# dsPIC.net
KiCad netlist of a schematic drawn in EAGLE
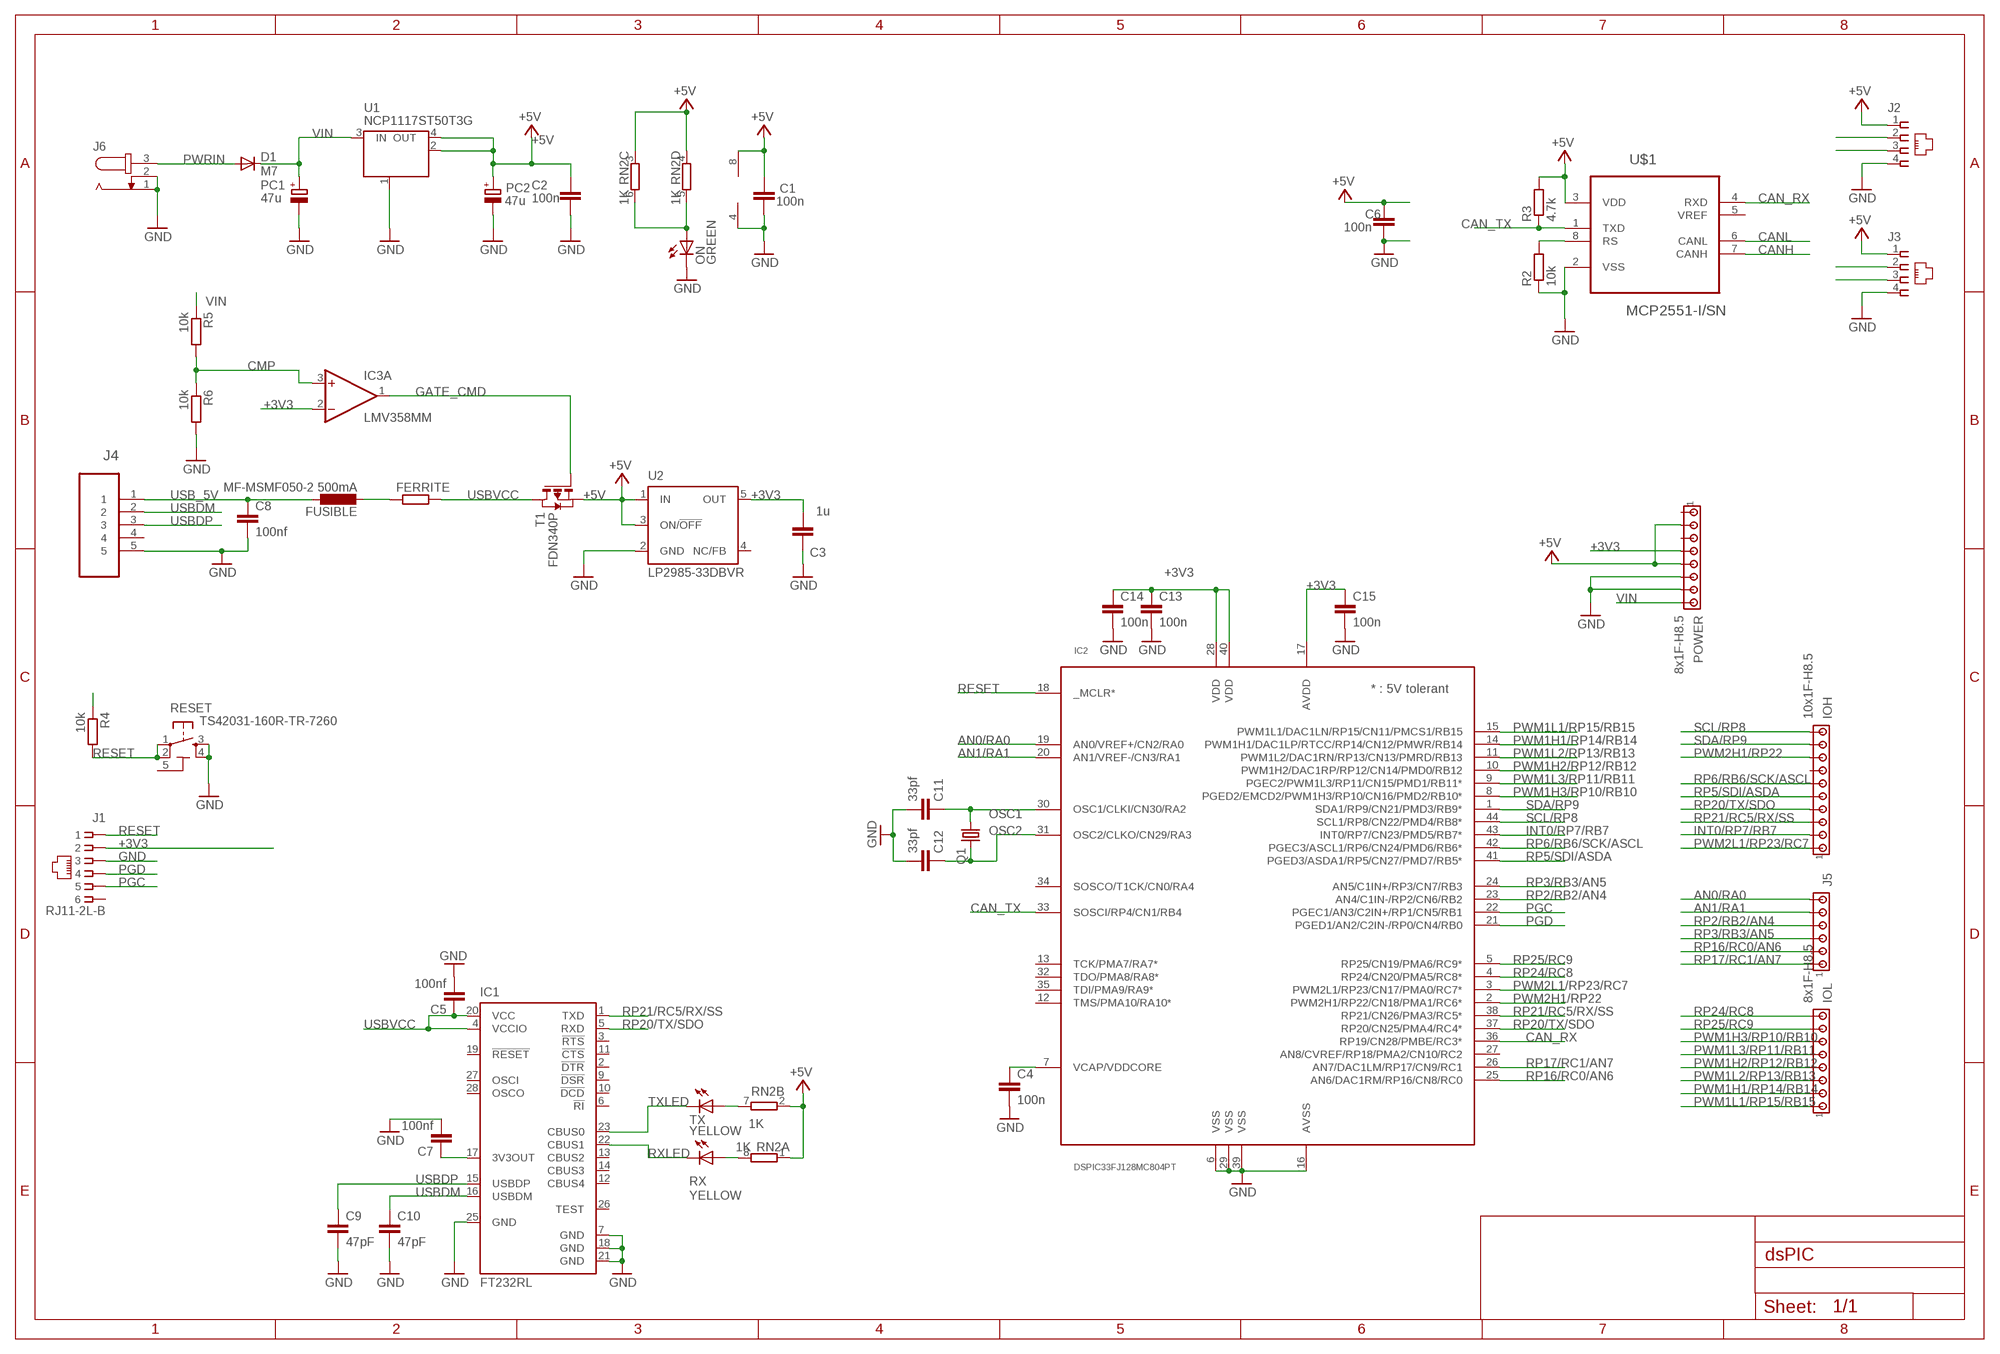
[diagram p0: schematic, sheet 1]

(export (version "E")
  (design (tool "Eeschema 10.0.6"))
  (components
    (comp (ref "C1")
      (value "100n")
      (footprint "eagle-import:C0603-ROUND")
      (libsource (lib "eagle-import") (part "C-EU0603-RND"))
    )
    (comp (ref "C2")
      (value "100n")
      (footprint "eagle-import:C0603-ROUND")
      (libsource (lib "eagle-import") (part "C-EU0603-RND"))
    )
    (comp (ref "C3")
      (value "1u")
      (footprint "eagle-import:C0603-ROUND")
      (libsource (lib "eagle-import") (part "C-EU0603-RND"))
    )
    (comp (ref "C4")
      (value "100n")
      (footprint "eagle-import:C0603K")
      (libsource (lib "eagle-import") (part "SmartPrj_C-EUC0603K"))
    )
    (comp (ref "C5")
      (value "100nf")
      (footprint "eagle-import:C0603")
      (libsource (lib "eagle-import") (part "C-EUC0603"))
    )
    (comp (ref "C6")
      (value "100n")
      (footprint "eagle-import:C0603K")
      (libsource (lib "eagle-import") (part "SmartPrj_C-EUC0603K"))
    )
    (comp (ref "C7")
      (value "100nf")
      (footprint "eagle-import:C0603")
      (libsource (lib "eagle-import") (part "C-EUC0603"))
    )
    (comp (ref "C8")
      (value "100nf")
      (footprint "eagle-import:C0603")
      (libsource (lib "eagle-import") (part "C-EUC0603"))
    )
    (comp (ref "C9")
      (value "47pF")
      (footprint "eagle-import:C0603")
      (libsource (lib "eagle-import") (part "C-EUC0603"))
    )
    (comp (ref "C10")
      (value "47pF")
      (footprint "eagle-import:C0603")
      (libsource (lib "eagle-import") (part "C-EUC0603"))
    )
    (comp (ref "C11")
      (value "33pf")
      (footprint "eagle-import:C0603")
      (libsource (lib "eagle-import") (part "C-EUC0603"))
    )
    (comp (ref "C12")
      (value "33pf")
      (footprint "eagle-import:C0603")
      (libsource (lib "eagle-import") (part "C-EUC0603"))
    )
    (comp (ref "C13")
      (value "100n")
      (footprint "eagle-import:C0603")
      (libsource (lib "eagle-import") (part "C-EUC0603"))
    )
    (comp (ref "C14")
      (value "100n")
      (footprint "eagle-import:C0603")
      (libsource (lib "eagle-import") (part "C-EUC0603"))
    )
    (comp (ref "C15")
      (value "100n")
      (footprint "eagle-import:C0603")
      (libsource (lib "eagle-import") (part "C-EUC0603"))
    )
    (comp (ref "D1")
      (value "M7")
      (footprint "eagle-import:SMB")
      (libsource (lib "eagle-import") (part "DIODE-SMB"))
    )
    (comp (ref "FERRITE")
      (value "R-EU_M0805")
      (footprint "eagle-import:M0805")
      (libsource (lib "eagle-import") (part "R-EU_M0805"))
    )
    (comp (ref "FUSIBLE")
      (value "MF-MSMF050-2 500mA")
      (footprint "eagle-import:L1812")
      (libsource (lib "eagle-import") (part "L-EUL1812"))
    )
    (comp (ref "IC1")
      (value "FT232RL")
      (footprint "eagle-import:SSOP28")
      (libsource (lib "eagle-import") (part "FT232RL"))
    )
    (comp (ref "IC2")
      (value "DSPIC33FJ128MC804PT")
      (footprint "eagle-import:TQFP44")
      (libsource (lib "eagle-import") (part "DSPIC33F04PTJ128MC8"))
    )
    (comp (ref "IC3")
      (value "LMV358MM")
      (footprint "eagle-import:MSOP08")
      (libsource (lib "eagle-import") (part "LMV358?MM"))
    )
    (comp (ref "IOH")
      (value "10x1F-H8.5")
      (footprint "eagle-import:10X10MTA")
      (libsource (lib "eagle-import") (part "MTA10-100"))
    )
    (comp (ref "IOL")
      (value "8x1F-H8.5")
      (footprint "eagle-import:10X08MTA")
      (libsource (lib "eagle-import") (part "MTA08-100"))
    )
    (comp (ref "J1")
      (value "RJ11-2L-B")
      (footprint "eagle-import:RJ11-NO_SHIELD")
      (fields (field (name "MF") "TYCO ELECTRONICS") (field (name "OC_FARNELL") "1393306"))
      (libsource (lib "eagle-import") (part "RJ11-2L-B"))
    )
    (comp (ref "J2")
      (value "520249-2")
      (footprint "eagle-import:520249-2")
      (libsource (lib "eagle-import") (part "520249-2"))
    )
    (comp (ref "J3")
      (value "520249-2")
      (footprint "eagle-import:520249-2")
      (libsource (lib "eagle-import") (part "520249-2"))
    )
    (comp (ref "J4")
      (value "47346-0001")
      (footprint "eagle-import:MOLEX_47346-0001")
      (libsource (lib "eagle-import") (part "47346-0001"))
    )
    (comp (ref "J5")
      (value "MTA06-100")
      (footprint "eagle-import:10X06MTA")
      (libsource (lib "eagle-import") (part "MTA06-100"))
    )
    (comp (ref "J6")
      (value "JACK-PLUG0")
      (footprint "eagle-import:SPC4077")
      (fields (field (name "OC_FARNELL") "1737246"))
      (libsource (lib "eagle-import") (part "JACK-PLUG0"))
    )
    (comp (ref "ON")
      (value "GREEN")
      (footprint "eagle-import:CHIP-LED0805")
      (libsource (lib "eagle-import") (part "LEDCHIP-LED0805"))
    )
    (comp (ref "PC1")
      (value "47u")
      (footprint "eagle-import:PANASONIC_D")
      (libsource (lib "eagle-import") (part "CPOL-EUD"))
    )
    (comp (ref "PC2")
      (value "47u")
      (footprint "eagle-import:PANASONIC_D")
      (libsource (lib "eagle-import") (part "CPOL-EUD"))
    )
    (comp (ref "POWER")
      (value "8x1F-H8.5")
      (footprint "eagle-import:10X08MTA")
      (libsource (lib "eagle-import") (part "MTA08-100"))
    )
    (comp (ref "Q1")
      (value "CRYSTALSM49")
      (footprint "eagle-import:SM49")
      (fields (field (name "OC_FARNELL") "1842332"))
      (libsource (lib "eagle-import") (part "CRYSTALSM49"))
    )
    (comp (ref "R2")
      (value "10k")
      (footprint "eagle-import:R0805")
      (libsource (lib "eagle-import") (part "R-EU_R0805"))
    )
    (comp (ref "R3")
      (value "4.7k")
      (footprint "eagle-import:R0805")
      (libsource (lib "eagle-import") (part "R-EU_R0805"))
    )
    (comp (ref "R4")
      (value "10k")
      (footprint "eagle-import:R0805")
      (libsource (lib "eagle-import") (part "R-EU_R0805"))
    )
    (comp (ref "R5")
      (value "10k")
      (footprint "eagle-import:R0805")
      (libsource (lib "eagle-import") (part "R-EU_R0805"))
    )
    (comp (ref "R6")
      (value "10k")
      (footprint "eagle-import:R0805")
      (libsource (lib "eagle-import") (part "R-EU_R0805"))
    )
    (comp (ref "RESET")
      (value "TS42031-160R-TR-7260")
      (footprint "eagle-import:TS42")
      (libsource (lib "eagle-import") (part "TS42"))
    )
    (comp (ref "RN2")
      (value "1K")
      (footprint "eagle-import:CAY16")
      (fields (field (name "OC_FARNELL") "2352761") (field (name "OC_NEWARK") "none"))
      (libsource (lib "eagle-import") (part "4R-NCAY16"))
    )
    (comp (ref "RX")
      (value "YELLOW")
      (footprint "eagle-import:CHIP-LED0805")
      (libsource (lib "eagle-import") (part "LEDCHIP-LED0805"))
    )
    (comp (ref "T1")
      (value "FDN340P")
      (footprint "eagle-import:SOT-23")
      (fields (field (name "OC_FARNELL") "9846310") (field (name "OC_NEWARK") "none"))
      (libsource (lib "eagle-import") (part "PMOSSOT23"))
    )
    (comp (ref "TX")
      (value "YELLOW")
      (footprint "eagle-import:CHIP-LED0805")
      (libsource (lib "eagle-import") (part "LEDCHIP-LED0805"))
    )
    (comp (ref "U$1")
      (value "MCP2551-I/SN")
      (footprint "eagle-import:SOIC127P600X175-8N")
      (libsource (lib "eagle-import") (part "MCP2551-I/SN"))
    )
    (comp (ref "U1")
      (value "NCP1117ST50T3G")
      (footprint "eagle-import:SOT223")
      (libsource (lib "eagle-import") (part "MC33269ST-3.3T3"))
    )
    (comp (ref "U2")
      (value "LP2985-33DBVR")
      (footprint "eagle-import:SOT23-DBV")
      (libsource (lib "eagle-import") (part "LP2985-XXDBVR33"))
    )
  )
  (nets
    (net (code "1") (name "+5V") (class "Default")
      (node (ref "C1") (pin "2") (pinfunction "2_2") (pintype "passive"))
      (node (ref "C2") (pin "2") (pinfunction "2_2") (pintype "passive"))
      (node (ref "C6") (pin "2") (pinfunction "2_2") (pintype "passive"))
      (node (ref "IC3") (pin "8") (pinfunction "V+_8") (pintype "power_in"))
      (node (ref "J2") (pin "1") (pinfunction "1_1") (pintype "passive"))
      (node (ref "J3") (pin "1") (pinfunction "1_1") (pintype "passive"))
      (node (ref "PC2") (pin "+") (pinfunction "+_+") (pintype "passive"))
      (node (ref "POWER") (pin "2") (pinfunction "2_2") (pintype "passive"))
      (node (ref "POWER") (pin "5") (pinfunction "5_5") (pintype "passive"))
      (node (ref "R3") (pin "2") (pinfunction "2_2") (pintype "passive"))
      (node (ref "RN2") (pin "1") (pinfunction "1_1") (pintype "passive"))
      (node (ref "RN2") (pin "2") (pinfunction "1_2") (pintype "passive"))
      (node (ref "RN2") (pin "3") (pinfunction "1_3") (pintype "passive"))
      (node (ref "RN2") (pin "4") (pinfunction "1_4") (pintype "passive"))
      (node (ref "T1") (pin "2") (pinfunction "S_2") (pintype "passive"))
      (node (ref "U$1") (pin "3") (pinfunction "VDD_3") (pintype "power_in"))
      (node (ref "U1") (pin "2") (pinfunction "OUT_2") (pintype "passive"))
      (node (ref "U1") (pin "4") (pinfunction "OUT_4") (pintype "passive"))
      (node (ref "U2") (pin "1") (pinfunction "IN_1") (pintype "input"))
      (node (ref "U2") (pin "3") (pinfunction "ON/~{OFF}_3") (pintype "input"))
    )
    (net (code "2") (name "/+3V3") (class "Default")
      (node (ref "C13") (pin "1") (pinfunction "1_1") (pintype "passive"))
      (node (ref "C14") (pin "1") (pinfunction "1_1") (pintype "passive"))
      (node (ref "C15") (pin "1") (pinfunction "1_1") (pintype "passive"))
      (node (ref "C3") (pin "2") (pinfunction "2_2") (pintype "passive"))
      (node (ref "IC2") (pin "17") (pinfunction "AVDD_17") (pintype "power_in"))
      (node (ref "IC2") (pin "28") (pinfunction "VDD_28") (pintype "power_in"))
      (node (ref "IC2") (pin "40") (pinfunction "VDD_40") (pintype "power_in"))
      (node (ref "IC3") (pin "2") (pinfunction "-IN_2") (pintype "input"))
      (node (ref "J1") (pin "2") (pinfunction "2_2") (pintype "passive"))
      (node (ref "POWER") (pin "4") (pinfunction "4_4") (pintype "passive"))
      (node (ref "R4") (pin "1") (pinfunction "1_1") (pintype "passive"))
      (node (ref "U2") (pin "5") (pinfunction "OUT_5") (pintype "passive"))
    )
    (net (code "3") (name "/5-GND") (class "Default")
      (node (ref "RESET") (pin "5") (pinfunction "5-GND_5") (pintype "power_in"))
    )
    (net (code "4") (name "/AN0{slash}RA0") (class "Default")
      (node (ref "IC2") (pin "19") (pinfunction "AN0/VREF+/CN2/RA0_19") (pintype "bidirectional"))
      (node (ref "J5") (pin "1") (pinfunction "6_1") (pintype "passive"))
    )
    (net (code "5") (name "/AN1{slash}RA1") (class "Default")
      (node (ref "IC2") (pin "20") (pinfunction "AN1/VREF-/CN3/RA1_20") (pintype "bidirectional"))
      (node (ref "J5") (pin "2") (pinfunction "5_2") (pintype "passive"))
    )
    (net (code "6") (name "/CANH") (class "Default")
      (node (ref "J2") (pin "2") (pinfunction "2_2") (pintype "passive"))
      (node (ref "J3") (pin "2") (pinfunction "2_2") (pintype "passive"))
      (node (ref "U$1") (pin "7") (pinfunction "CANH_7") (pintype "bidirectional"))
    )
    (net (code "7") (name "/CANL") (class "Default")
      (node (ref "J2") (pin "3") (pinfunction "3_3") (pintype "passive"))
      (node (ref "J3") (pin "3") (pinfunction "3_3") (pintype "passive"))
      (node (ref "U$1") (pin "6") (pinfunction "CANL_6") (pintype "bidirectional"))
    )
    (net (code "8") (name "/CAN_RX") (class "Default")
      (node (ref "IC2") (pin "36") (pinfunction "RP19/CN28/PMBE/RC3*_36") (pintype "bidirectional"))
      (node (ref "U$1") (pin "4") (pinfunction "RXD_4") (pintype "output"))
    )
    (net (code "9") (name "/CAN_TX") (class "Default")
      (node (ref "IC2") (pin "33") (pinfunction "SOSCI/RP4/CN1/RB4_33") (pintype "bidirectional"))
      (node (ref "R3") (pin "1") (pinfunction "1_1") (pintype "passive"))
      (node (ref "U$1") (pin "1") (pinfunction "TXD_1") (pintype "input"))
    )
    (net (code "10") (name "/CMP") (class "Default")
      (node (ref "IC3") (pin "3") (pinfunction "+IN_3") (pintype "input"))
      (node (ref "R5") (pin "2") (pinfunction "2_2") (pintype "passive"))
      (node (ref "R6") (pin "1") (pinfunction "1_1") (pintype "passive"))
    )
    (net (code "11") (name "/GATE_CMD") (class "Default")
      (node (ref "IC3") (pin "1") (pinfunction "OUT_1") (pintype "output"))
      (node (ref "T1") (pin "3") (pinfunction "G_3") (pintype "passive"))
    )
    (net (code "12") (name "/INT0{slash}RP7{slash}RB7") (class "Default")
      (node (ref "IC2") (pin "43") (pinfunction "INT0/RP7/CN23/PMD5/RB7*_43") (pintype "bidirectional"))
      (node (ref "IOH") (pin "2") (pinfunction "2_2") (pintype "passive"))
    )
    (net (code "13") (name "/OSC1") (class "Default")
      (node (ref "C11") (pin "1") (pinfunction "1_1") (pintype "passive"))
      (node (ref "IC2") (pin "30") (pinfunction "OSC1/CLKI/CN30/RA2_30") (pintype "bidirectional"))
      (node (ref "Q1") (pin "1") (pinfunction "1_1") (pintype "passive"))
    )
    (net (code "14") (name "/OSC2") (class "Default")
      (node (ref "C12") (pin "1") (pinfunction "1_1") (pintype "passive"))
      (node (ref "IC2") (pin "31") (pinfunction "OSC2/CLKO/CN29/RA3_31") (pintype "bidirectional"))
      (node (ref "Q1") (pin "2") (pinfunction "2_2") (pintype "passive"))
    )
    (net (code "15") (name "/PGC") (class "Default")
      (node (ref "IC2") (pin "22") (pinfunction "PGEC1/AN3/C2IN+/RP1/CN5/RB1_22") (pintype "bidirectional"))
      (node (ref "J1") (pin "5") (pinfunction "5_5") (pintype "passive"))
    )
    (net (code "16") (name "/PGD") (class "Default")
      (node (ref "IC2") (pin "21") (pinfunction "PGED1/AN2/C2IN-/RP0/CN4/RB0_21") (pintype "bidirectional"))
      (node (ref "J1") (pin "4") (pinfunction "4_4") (pintype "passive"))
    )
    (net (code "17") (name "/PWM1H1{slash}RP14{slash}RB14") (class "Default")
      (node (ref "IC2") (pin "14") (pinfunction "PWM1H1/DAC1LP/RTCC/RP14/CN12/PMWR/RB14_14") (pintype "bidirectional"))
      (node (ref "IOL") (pin "2") (pinfunction "2_2") (pintype "passive"))
    )
    (net (code "18") (name "/PWM1H2{slash}RP12{slash}RB12") (class "Default")
      (node (ref "IC2") (pin "10") (pinfunction "PWM1H2/DAC1RP/RP12/CN14/PMD0/RB12_10") (pintype "bidirectional"))
      (node (ref "IOL") (pin "4") (pinfunction "4_4") (pintype "passive"))
    )
    (net (code "19") (name "/PWM1H3{slash}RP10{slash}RB10") (class "Default")
      (node (ref "IC2") (pin "8") (pinfunction "PGED2/EMCD2/PWM1H3/RP10/CN16/PMD2/RB10*_8") (pintype "bidirectional"))
      (node (ref "IOL") (pin "6") (pinfunction "6_6") (pintype "passive"))
    )
    (net (code "20") (name "/PWM1L1{slash}RP15{slash}RB15") (class "Default")
      (node (ref "IC2") (pin "15") (pinfunction "PWM1L1/DAC1LN/RP15/CN11/PMCS1/RB15_15") (pintype "bidirectional"))
      (node (ref "IOL") (pin "1") (pinfunction "1_1") (pintype "passive"))
    )
    (net (code "21") (name "/PWM1L2{slash}RP13{slash}RB13") (class "Default")
      (node (ref "IC2") (pin "11") (pinfunction "PWM1L2/DAC1RN/RP13/CN13/PMRD/RB13_11") (pintype "bidirectional"))
      (node (ref "IOL") (pin "3") (pinfunction "3_3") (pintype "passive"))
    )
    (net (code "22") (name "/PWM1L3{slash}RP11{slash}RB11") (class "Default")
      (node (ref "IC2") (pin "9") (pinfunction "PGEC2/PWM1L3/RP11/CN15/PMD1/RB11*_9") (pintype "bidirectional"))
      (node (ref "IOL") (pin "5") (pinfunction "5_5") (pintype "passive"))
    )
    (net (code "23") (name "/PWM2H1{slash}RP22") (class "Default")
      (node (ref "IC2") (pin "2") (pinfunction "PWM2H1/RP22/CN18/PMA1/RC6*_2") (pintype "bidirectional"))
      (node (ref "IOH") (pin "8") (pinfunction "8_8") (pintype "passive"))
    )
    (net (code "24") (name "/PWM2L1{slash}RP23{slash}RC7") (class "Default")
      (node (ref "IC2") (pin "3") (pinfunction "PWM2L1/RP23/CN17/PMA0/RC7*_3") (pintype "bidirectional"))
      (node (ref "IOH") (pin "1") (pinfunction "1_1") (pintype "passive"))
    )
    (net (code "25") (name "/PWRIN") (class "Default")
      (node (ref "D1") (pin "A") (pinfunction "A_A") (pintype "passive"))
      (node (ref "J6") (pin "3") (pinfunction "3_3") (pintype "passive"))
    )
    (net (code "26") (name "/RESET") (class "Default")
      (node (ref "IC2") (pin "18") (pinfunction "_MCLR*_18") (pintype "input"))
      (node (ref "J1") (pin "1") (pinfunction "1_1") (pintype "passive"))
      (node (ref "R4") (pin "2") (pinfunction "2_2") (pintype "passive"))
      (node (ref "RESET") (pin "1") (pinfunction "1_1") (pintype "passive"))
      (node (ref "RESET") (pin "2") (pinfunction "2_2") (pintype "passive"))
    )
    (net (code "27") (name "/RP2{slash}RB2{slash}AN4") (class "Default")
      (node (ref "IC2") (pin "23") (pinfunction "AN4/C1IN-/RP2/CN6/RB2_23") (pintype "bidirectional"))
      (node (ref "J5") (pin "3") (pinfunction "4_3") (pintype "passive"))
    )
    (net (code "28") (name "/RP3{slash}RB3{slash}AN5") (class "Default")
      (node (ref "IC2") (pin "24") (pinfunction "AN5/C1IN+/RP3/CN7/RB3_24") (pintype "bidirectional"))
      (node (ref "J5") (pin "4") (pinfunction "3_4") (pintype "passive"))
    )
    (net (code "29") (name "/RP5{slash}SDI{slash}ASDA") (class "Default")
      (node (ref "IC2") (pin "41") (pinfunction "PGED3/ASDA1/RP5/CN27/PMD7/RB5*_41") (pintype "bidirectional"))
      (node (ref "IOH") (pin "5") (pinfunction "5_5") (pintype "passive"))
    )
    (net (code "30") (name "/RP6{slash}RB6{slash}SCK{slash}ASCL") (class "Default")
      (node (ref "IC2") (pin "42") (pinfunction "PGEC3/ASCL1/RP6/CN24/PMD6/RB6*_42") (pintype "bidirectional"))
      (node (ref "IOH") (pin "6") (pinfunction "6_6") (pintype "passive"))
    )
    (net (code "31") (name "/RP16{slash}RC0{slash}AN6") (class "Default")
      (node (ref "IC2") (pin "25") (pinfunction "AN6/DAC1RM/RP16/CN8/RC0_25") (pintype "bidirectional"))
      (node (ref "J5") (pin "5") (pinfunction "2_5") (pintype "passive"))
    )
    (net (code "32") (name "/RP17{slash}RC1{slash}AN7") (class "Default")
      (node (ref "IC2") (pin "26") (pinfunction "AN7/DAC1LM/RP17/CN9/RC1_26") (pintype "bidirectional"))
      (node (ref "J5") (pin "6") (pinfunction "1_6") (pintype "passive"))
    )
    (net (code "33") (name "/RP20{slash}TX{slash}SDO") (class "Default")
      (node (ref "IC1") (pin "5") (pinfunction "RXD_5") (pintype "input"))
      (node (ref "IC2") (pin "37") (pinfunction "RP20/CN25/PMA4/RC4*_37") (pintype "bidirectional"))
      (node (ref "IOH") (pin "4") (pinfunction "4_4") (pintype "passive"))
    )
    (net (code "34") (name "/RP21{slash}RC5{slash}RX{slash}SS") (class "Default")
      (node (ref "IC1") (pin "1") (pinfunction "TXD_1") (pintype "output"))
      (node (ref "IC2") (pin "38") (pinfunction "RP21/CN26/PMA3/RC5*_38") (pintype "bidirectional"))
      (node (ref "IOH") (pin "3") (pinfunction "3_3") (pintype "passive"))
    )
    (net (code "35") (name "/RP24{slash}RC8") (class "Default")
      (node (ref "IC2") (pin "4") (pinfunction "RP24/CN20/PMA5/RC8*_4") (pintype "bidirectional"))
      (node (ref "IOL") (pin "8") (pinfunction "8_8") (pintype "passive"))
    )
    (net (code "36") (name "/RP25{slash}RC9") (class "Default")
      (node (ref "IC2") (pin "5") (pinfunction "RP25/CN19/PMA6/RC9*_5") (pintype "bidirectional"))
      (node (ref "IOL") (pin "7") (pinfunction "7_7") (pintype "passive"))
    )
    (net (code "37") (name "/RXLED") (class "Default")
      (node (ref "IC1") (pin "22") (pinfunction "CBUS1_22") (pintype "bidirectional"))
      (node (ref "RX") (pin "C") (pinfunction "C_C") (pintype "passive"))
    )
    (net (code "38") (name "/SCL{slash}RP8") (class "Default")
      (node (ref "IC2") (pin "44") (pinfunction "SCL1/RP8/CN22/PMD4/RB8*_44") (pintype "bidirectional"))
      (node (ref "IOH") (pin "10") (pinfunction "10_10") (pintype "passive"))
    )
    (net (code "39") (name "/SDA{slash}RP9") (class "Default")
      (node (ref "IC2") (pin "1") (pinfunction "SDA1/RP9/CN21/PMD3/RB9*_1") (pintype "bidirectional"))
      (node (ref "IOH") (pin "9") (pinfunction "9_9") (pintype "passive"))
    )
    (net (code "40") (name "/TXLED") (class "Default")
      (node (ref "IC1") (pin "23") (pinfunction "CBUS0_23") (pintype "bidirectional"))
      (node (ref "TX") (pin "C") (pinfunction "C_C") (pintype "passive"))
    )
    (net (code "41") (name "/USBDM") (class "Default")
      (node (ref "C10") (pin "1") (pinfunction "1_1") (pintype "passive"))
      (node (ref "IC1") (pin "16") (pinfunction "USBDM_16") (pintype "bidirectional"))
      (node (ref "J4") (pin "2") (pinfunction "2_2") (pintype "input"))
    )
    (net (code "42") (name "/USBDP") (class "Default")
      (node (ref "C9") (pin "1") (pinfunction "1_1") (pintype "passive"))
      (node (ref "IC1") (pin "15") (pinfunction "USBDP_15") (pintype "bidirectional"))
      (node (ref "J4") (pin "3") (pinfunction "3_3") (pintype "input"))
    )
    (net (code "43") (name "/USBVCC") (class "Default")
      (node (ref "C5") (pin "1") (pinfunction "1_1") (pintype "passive"))
      (node (ref "FERRITE") (pin "2") (pinfunction "2_2") (pintype "passive"))
      (node (ref "IC1") (pin "20") (pinfunction "VCC_20") (pintype "power_in"))
      (node (ref "IC1") (pin "4") (pinfunction "VCCIO_4") (pintype "power_in"))
      (node (ref "T1") (pin "1") (pinfunction "D_1") (pintype "passive"))
    )
    (net (code "44") (name "/USB_5V") (class "Default")
      (node (ref "C8") (pin "1") (pinfunction "1_1") (pintype "passive"))
      (node (ref "FUSIBLE") (pin "1") (pinfunction "1_1") (pintype "passive"))
      (node (ref "J4") (pin "1") (pinfunction "1_1") (pintype "input"))
    )
    (net (code "45") (name "/VIN") (class "Default")
      (node (ref "D1") (pin "C") (pinfunction "C_C") (pintype "passive"))
      (node (ref "PC1") (pin "+") (pinfunction "+_+") (pintype "passive"))
      (node (ref "POWER") (pin "8") (pinfunction "8_8") (pintype "passive"))
      (node (ref "R5") (pin "1") (pinfunction "1_1") (pintype "passive"))
      (node (ref "U1") (pin "3") (pinfunction "IN_3") (pintype "input"))
    )
    (net (code "46") (name "GND") (class "Default")
      (node (ref "C1") (pin "1") (pinfunction "1_1") (pintype "passive"))
      (node (ref "C10") (pin "2") (pinfunction "2_2") (pintype "passive"))
      (node (ref "C11") (pin "2") (pinfunction "2_2") (pintype "passive"))
      (node (ref "C12") (pin "2") (pinfunction "2_2") (pintype "passive"))
      (node (ref "C13") (pin "2") (pinfunction "2_2") (pintype "passive"))
      (node (ref "C14") (pin "2") (pinfunction "2_2") (pintype "passive"))
      (node (ref "C15") (pin "2") (pinfunction "2_2") (pintype "passive"))
      (node (ref "C2") (pin "1") (pinfunction "1_1") (pintype "passive"))
      (node (ref "C3") (pin "1") (pinfunction "1_1") (pintype "passive"))
      (node (ref "C4") (pin "2") (pinfunction "2_2") (pintype "passive"))
      (node (ref "C5") (pin "2") (pinfunction "2_2") (pintype "passive"))
      (node (ref "C6") (pin "1") (pinfunction "1_1") (pintype "passive"))
      (node (ref "C7") (pin "2") (pinfunction "2_2") (pintype "passive"))
      (node (ref "C8") (pin "2") (pinfunction "2_2") (pintype "passive"))
      (node (ref "C9") (pin "2") (pinfunction "2_2") (pintype "passive"))
      (node (ref "IC1") (pin "18") (pinfunction "GND_18") (pintype "power_in"))
      (node (ref "IC1") (pin "21") (pinfunction "GND_21") (pintype "power_in"))
      (node (ref "IC1") (pin "25") (pinfunction "GND_25") (pintype "power_in"))
      (node (ref "IC1") (pin "7") (pinfunction "GND_7") (pintype "power_in"))
      (node (ref "IC2") (pin "16") (pinfunction "AVSS_16") (pintype "power_in"))
      (node (ref "IC2") (pin "29") (pinfunction "VSS_29") (pintype "power_in"))
      (node (ref "IC2") (pin "39") (pinfunction "VSS_39") (pintype "power_in"))
      (node (ref "IC2") (pin "6") (pinfunction "VSS_6") (pintype "power_in"))
      (node (ref "IC3") (pin "4") (pinfunction "V-_4") (pintype "power_in"))
      (node (ref "J1") (pin "3") (pinfunction "3_3") (pintype "passive"))
      (node (ref "J2") (pin "4") (pinfunction "4_4") (pintype "passive"))
      (node (ref "J3") (pin "4") (pinfunction "4_4") (pintype "passive"))
      (node (ref "J4") (pin "5") (pinfunction "5_5") (pintype "input"))
      (node (ref "J6") (pin "1") (pinfunction "1_1") (pintype "passive"))
      (node (ref "J6") (pin "2") (pinfunction "2_2") (pintype "passive"))
      (node (ref "ON") (pin "C") (pinfunction "C_C") (pintype "passive"))
      (node (ref "PC1") (pin "-") (pinfunction "-_-") (pintype "passive"))
      (node (ref "PC2") (pin "-") (pinfunction "-_-") (pintype "passive"))
      (node (ref "POWER") (pin "6") (pinfunction "6_6") (pintype "passive"))
      (node (ref "POWER") (pin "7") (pinfunction "7_7") (pintype "passive"))
      (node (ref "R2") (pin "1") (pinfunction "1_1") (pintype "passive"))
      (node (ref "R6") (pin "2") (pinfunction "2_2") (pintype "passive"))
      (node (ref "RESET") (pin "3") (pinfunction "3_3") (pintype "passive"))
      (node (ref "RESET") (pin "4") (pinfunction "4_4") (pintype "passive"))
      (node (ref "U$1") (pin "2") (pinfunction "VSS_2") (pintype "passive"))
      (node (ref "U1") (pin "1") (pinfunction "GND/ADJ_1") (pintype "input"))
      (node (ref "U2") (pin "2") (pinfunction "GND_2") (pintype "power_in"))
    )
    (net (code "47") (name "Net-(FERRITE-Pad1)") (class "Default")
      (node (ref "FERRITE") (pin "1") (pinfunction "1_1") (pintype "passive"))
      (node (ref "FUSIBLE") (pin "2") (pinfunction "2_2") (pintype "passive"))
    )
    (net (code "48") (name "Net-(IC1-3V3OUT)") (class "Default")
      (node (ref "C7") (pin "1") (pinfunction "1_1") (pintype "passive"))
      (node (ref "IC1") (pin "17") (pinfunction "3V3OUT_17") (pintype "output"))
    )
    (net (code "49") (name "Net-(IC2-VCAP{slash}VDDCORE)") (class "Default")
      (node (ref "C4") (pin "1") (pinfunction "1_1") (pintype "passive"))
      (node (ref "IC2") (pin "7") (pinfunction "VCAP/VDDCORE_7") (pintype "power_in"))
    )
    (net (code "50") (name "Net-(RN2A-2)") (class "Default")
      (node (ref "RN2") (pin "8") (pinfunction "2_8") (pintype "passive"))
      (node (ref "RX") (pin "A") (pinfunction "A_A") (pintype "passive"))
    )
    (net (code "51") (name "Net-(RN2B-2)") (class "Default")
      (node (ref "RN2") (pin "7") (pinfunction "2_7") (pintype "passive"))
      (node (ref "TX") (pin "A") (pinfunction "A_A") (pintype "passive"))
    )
    (net (code "52") (name "Net-(RN2C-2)") (class "Default")
      (node (ref "ON") (pin "A") (pinfunction "A_A") (pintype "passive"))
      (node (ref "RN2") (pin "5") (pinfunction "2_5") (pintype "passive"))
      (node (ref "RN2") (pin "6") (pinfunction "2_6") (pintype "passive"))
    )
    (net (code "53") (name "Net-(U$1-RS)") (class "Default")
      (node (ref "R2") (pin "2") (pinfunction "2_2") (pintype "passive"))
      (node (ref "U$1") (pin "8") (pinfunction "RS_8") (pintype "input"))
    )
    (net (code "54") (name "unconnected-(IC1-CBUS2-Pad13)") (class "Default")
      (node (ref "IC1") (pin "13") (pinfunction "CBUS2_13") (pintype "bidirectional"))
    )
    (net (code "55") (name "unconnected-(IC1-CBUS3-Pad14)") (class "Default")
      (node (ref "IC1") (pin "14") (pinfunction "CBUS3_14") (pintype "bidirectional"))
    )
    (net (code "56") (name "unconnected-(IC1-CBUS4-Pad12)") (class "Default")
      (node (ref "IC1") (pin "12") (pinfunction "CBUS4_12") (pintype "bidirectional"))
    )
    (net (code "57") (name "unconnected-(IC1-OSCI-Pad27)") (class "Default")
      (node (ref "IC1") (pin "27") (pinfunction "OSCI_27") (pintype "input"))
    )
    (net (code "58") (name "unconnected-(IC1-OSCO-Pad28)") (class "Default")
      (node (ref "IC1") (pin "28") (pinfunction "OSCO_28") (pintype "output"))
    )
    (net (code "59") (name "unconnected-(IC1-TEST-Pad26)") (class "Default")
      (node (ref "IC1") (pin "26") (pinfunction "TEST_26") (pintype "input"))
    )
    (net (code "60") (name "unconnected-(IC1-~{CTS}-Pad11)") (class "Default")
      (node (ref "IC1") (pin "11") (pinfunction "~{CTS}_11") (pintype "input"))
    )
    (net (code "61") (name "unconnected-(IC1-~{DCD}-Pad10)") (class "Default")
      (node (ref "IC1") (pin "10") (pinfunction "~{DCD}_10") (pintype "input"))
    )
    (net (code "62") (name "unconnected-(IC1-~{DSR}-Pad9)") (class "Default")
      (node (ref "IC1") (pin "9") (pinfunction "~{DSR}_9") (pintype "input"))
    )
    (net (code "63") (name "unconnected-(IC1-~{DTR}-Pad2)") (class "Default")
      (node (ref "IC1") (pin "2") (pinfunction "~{DTR}_2") (pintype "output"))
    )
    (net (code "64") (name "unconnected-(IC1-~{RESET}-Pad19)") (class "Default")
      (node (ref "IC1") (pin "19") (pinfunction "~{RESET}_19") (pintype "input"))
    )
    (net (code "65") (name "unconnected-(IC1-~{RI}-Pad6)") (class "Default")
      (node (ref "IC1") (pin "6") (pinfunction "~{RI}_6") (pintype "input"))
    )
    (net (code "66") (name "unconnected-(IC1-~{RTS}-Pad3)") (class "Default")
      (node (ref "IC1") (pin "3") (pinfunction "~{RTS}_3") (pintype "output"))
    )
    (net (code "67") (name "unconnected-(IC2-AN8{slash}CVREF{slash}RP18{slash}PMA2{slash}CN10{slash}RC2-Pad27)") (class "Default")
      (node (ref "IC2") (pin "27") (pinfunction "AN8/CVREF/RP18/PMA2/CN10/RC2_27") (pintype "bidirectional"))
    )
    (net (code "68") (name "unconnected-(IC2-SOSCO{slash}T1CK{slash}CN0{slash}RA4-Pad34)") (class "Default")
      (node (ref "IC2") (pin "34") (pinfunction "SOSCO/T1CK/CN0/RA4_34") (pintype "bidirectional"))
    )
    (net (code "69") (name "unconnected-(IC2-TCK{slash}PMA7{slash}RA7*-Pad13)") (class "Default")
      (node (ref "IC2") (pin "13") (pinfunction "TCK/PMA7/RA7*_13") (pintype "bidirectional"))
    )
    (net (code "70") (name "unconnected-(IC2-TDI{slash}PMA9{slash}RA9*-Pad35)") (class "Default")
      (node (ref "IC2") (pin "35") (pinfunction "TDI/PMA9/RA9*_35") (pintype "bidirectional"))
    )
    (net (code "71") (name "unconnected-(IC2-TDO{slash}PMA8{slash}RA8*-Pad32)") (class "Default")
      (node (ref "IC2") (pin "32") (pinfunction "TDO/PMA8/RA8*_32") (pintype "bidirectional"))
    )
    (net (code "72") (name "unconnected-(IC2-TMS{slash}PMA10{slash}RA10*-Pad12)") (class "Default")
      (node (ref "IC2") (pin "12") (pinfunction "TMS/PMA10/RA10*_12") (pintype "bidirectional"))
    )
    (net (code "73") (name "unconnected-(IOH-Pad7)") (class "Default")
      (node (ref "IOH") (pin "7") (pinfunction "7_7") (pintype "passive"))
    )
    (net (code "74") (name "unconnected-(J1-Pad6)") (class "Default")
      (node (ref "J1") (pin "6") (pinfunction "6_6") (pintype "passive"))
    )
    (net (code "75") (name "unconnected-(J4-Pad4)") (class "Default")
      (node (ref "J4") (pin "4") (pinfunction "4_4") (pintype "input"))
    )
    (net (code "76") (name "unconnected-(POWER-Pad1)") (class "Default")
      (node (ref "POWER") (pin "1") (pinfunction "1_1") (pintype "passive"))
    )
    (net (code "77") (name "unconnected-(POWER-Pad3)") (class "Default")
      (node (ref "POWER") (pin "3") (pinfunction "3_3") (pintype "passive"))
    )
    (net (code "78") (name "unconnected-(U$1-VREF-Pad5)") (class "Default")
      (node (ref "U$1") (pin "5") (pinfunction "VREF_5") (pintype "output"))
    )
    (net (code "79") (name "unconnected-(U2-NC{slash}FB-Pad4)") (class "Default")
      (node (ref "U2") (pin "4") (pinfunction "NC/FB_4") (pintype "passive"))
    )
  )
)
